# Shift_register.net
KiCad netlist of a schematic drawn in Altium Designer
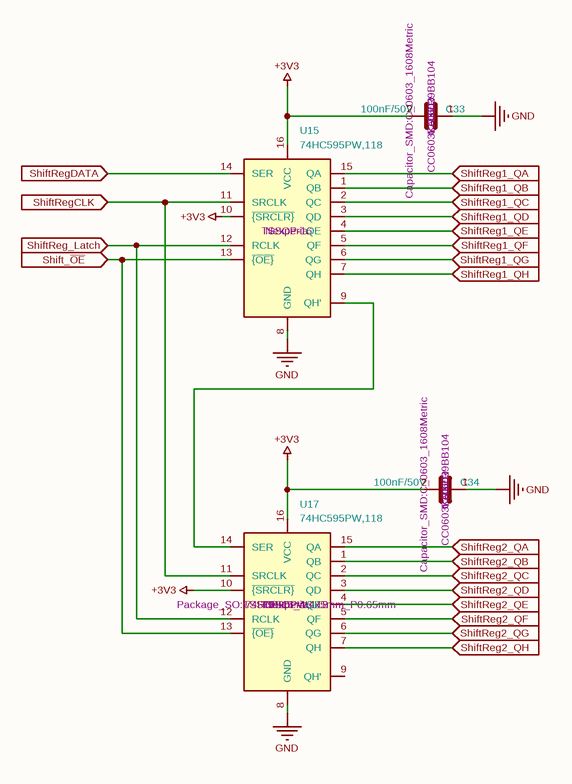
[diagram p0: Shift register.SchDoc]

(export (version "E")
  (design (tool "Eeschema 10.0.6"))
  (components
    (comp (ref "C33")
      (value "100nF/50V")
      (footprint "Capacitor_SMD:C_0603_1608Metric")
      (fields
        (field (name "MANUFACTURER PART NUMBER") "CC0603KRX7R9BB104")
        (field (name "MANUFACTURER") "YAGEO")
        (field (name "PACKAGE") "C_0603")
      )
      (libsource (lib "Device") (part "C"))
    )
    (comp (ref "C34")
      (value "100nF/50V")
      (footprint "Capacitor_SMD:C_0603_1608Metric")
      (fields
        (field (name "MANUFACTURER PART NUMBER") "CC0603KRX7R9BB104")
        (field (name "MANUFACTURER") "YAGEO")
        (field (name "PACKAGE") "C_0603")
      )
      (libsource (lib "Device") (part "C"))
    )
    (comp (ref "U15")
      (value "74HC595PW,118")
      (footprint "TSSOP-16_4.4x5mm_P0.65mm")
      (fields (field (name "MANUFACTURER") "Nexperia") (field (name "PACKAGE") "TSSOP-16"))
      (libsource (lib "74xx") (part "74HC595"))
    )
    (comp (ref "U17")
      (value "74HC595PW,118")
      (footprint "Package_SO:TSSOP-16_4.4x5mm_P0.65mm")
      (fields
        (field (name "MANUFACTURER PART NUMBER") "74HC595PW,118")
        (field (name "MANUFACTURER") "Nexperia")
        (field (name "PACKAGE") "TSSOP-16")
      )
      (libsource (lib "74xx") (part "74HC595"))
    )
  )
  (nets
    (net (code "1") (name "+3V3") (class "Default")
      (node (ref "C33") (pin "2") (pinfunction "2_2") (pintype "passive"))
      (node (ref "C34") (pin "2") (pinfunction "2_2") (pintype "passive"))
      (node (ref "U15") (pin "10") (pinfunction "~{{SRCLR}}_10") (pintype "passive"))
      (node (ref "U15") (pin "16") (pinfunction "VCC_16") (pintype "passive"))
      (node (ref "U17") (pin "10") (pinfunction "~{{SRCLR}}_10") (pintype "passive"))
      (node (ref "U17") (pin "16") (pinfunction "VCC_16") (pintype "passive"))
    )
    (net (code "2") (name "/ShiftReg1_QA") (class "Default")
      (node (ref "U15") (pin "15") (pinfunction "QA_15") (pintype "passive"))
    )
    (net (code "3") (name "/ShiftReg1_QB") (class "Default")
      (node (ref "U15") (pin "1") (pinfunction "QB_1") (pintype "passive"))
    )
    (net (code "4") (name "/ShiftReg1_QC") (class "Default")
      (node (ref "U15") (pin "2") (pinfunction "QC_2") (pintype "passive"))
    )
    (net (code "5") (name "/ShiftReg1_QD") (class "Default")
      (node (ref "U15") (pin "3") (pinfunction "QD_3") (pintype "passive"))
    )
    (net (code "6") (name "/ShiftReg1_QE") (class "Default")
      (node (ref "U15") (pin "4") (pinfunction "QE_4") (pintype "passive"))
    )
    (net (code "7") (name "/ShiftReg1_QF") (class "Default")
      (node (ref "U15") (pin "5") (pinfunction "QF_5") (pintype "passive"))
    )
    (net (code "8") (name "/ShiftReg1_QG") (class "Default")
      (node (ref "U15") (pin "6") (pinfunction "QG_6") (pintype "passive"))
    )
    (net (code "9") (name "/ShiftReg1_QH") (class "Default")
      (node (ref "U15") (pin "7") (pinfunction "QH_7") (pintype "passive"))
    )
    (net (code "10") (name "/ShiftReg2_QA") (class "Default")
      (node (ref "U17") (pin "15") (pinfunction "QA_15") (pintype "passive"))
    )
    (net (code "11") (name "/ShiftReg2_QB") (class "Default")
      (node (ref "U17") (pin "1") (pinfunction "QB_1") (pintype "passive"))
    )
    (net (code "12") (name "/ShiftReg2_QC") (class "Default")
      (node (ref "U17") (pin "2") (pinfunction "QC_2") (pintype "passive"))
    )
    (net (code "13") (name "/ShiftReg2_QD") (class "Default")
      (node (ref "U17") (pin "3") (pinfunction "QD_3") (pintype "passive"))
    )
    (net (code "14") (name "/ShiftReg2_QE") (class "Default")
      (node (ref "U17") (pin "4") (pinfunction "QE_4") (pintype "passive"))
    )
    (net (code "15") (name "/ShiftReg2_QF") (class "Default")
      (node (ref "U17") (pin "5") (pinfunction "QF_5") (pintype "passive"))
    )
    (net (code "16") (name "/ShiftReg2_QG") (class "Default")
      (node (ref "U17") (pin "6") (pinfunction "QG_6") (pintype "passive"))
    )
    (net (code "17") (name "/ShiftReg2_QH") (class "Default")
      (node (ref "U17") (pin "7") (pinfunction "QH_7") (pintype "passive"))
    )
    (net (code "18") (name "/ShiftRegCLK") (class "Default")
      (node (ref "U15") (pin "11") (pinfunction "SRCLK_11") (pintype "passive"))
      (node (ref "U17") (pin "11") (pinfunction "SRCLK_11") (pintype "passive"))
    )
    (net (code "19") (name "/ShiftRegDATA") (class "Default")
      (node (ref "U15") (pin "14") (pinfunction "SER_14") (pintype "passive"))
    )
    (net (code "20") (name "/ShiftReg_Latch") (class "Default")
      (node (ref "U15") (pin "12") (pinfunction "RCLK_12") (pintype "passive"))
      (node (ref "U17") (pin "12") (pinfunction "RCLK_12") (pintype "passive"))
    )
    (net (code "21") (name "/Shift_~{OE}") (class "Default")
      (node (ref "U15") (pin "13") (pinfunction "~{{OE}}_13") (pintype "passive"))
      (node (ref "U17") (pin "13") (pinfunction "~{{OE}}_13") (pintype "passive"))
    )
    (net (code "22") (name "GND") (class "Default")
      (node (ref "C33") (pin "1") (pinfunction "1_1") (pintype "passive"))
      (node (ref "C34") (pin "1") (pinfunction "1_1") (pintype "passive"))
      (node (ref "U15") (pin "8") (pinfunction "GND_8") (pintype "passive"))
      (node (ref "U17") (pin "8") (pinfunction "GND_8") (pintype "passive"))
    )
    (net (code "23") (name "Net-(U15-QH')") (class "Default")
      (node (ref "U15") (pin "9") (pinfunction "QH'_9") (pintype "passive"))
      (node (ref "U17") (pin "14") (pinfunction "SER_14") (pintype "passive"))
    )
    (net (code "24") (name "unconnected-(U17-QH'-Pad9)") (class "Default")
      (node (ref "U17") (pin "9") (pinfunction "QH'_9") (pintype "passive"))
    )
  )
)
